# SCH_5_5-OLED-to-RP5-MIPI_2025-08-24.net
KiCad netlist of a schematic drawn in EasyEDA
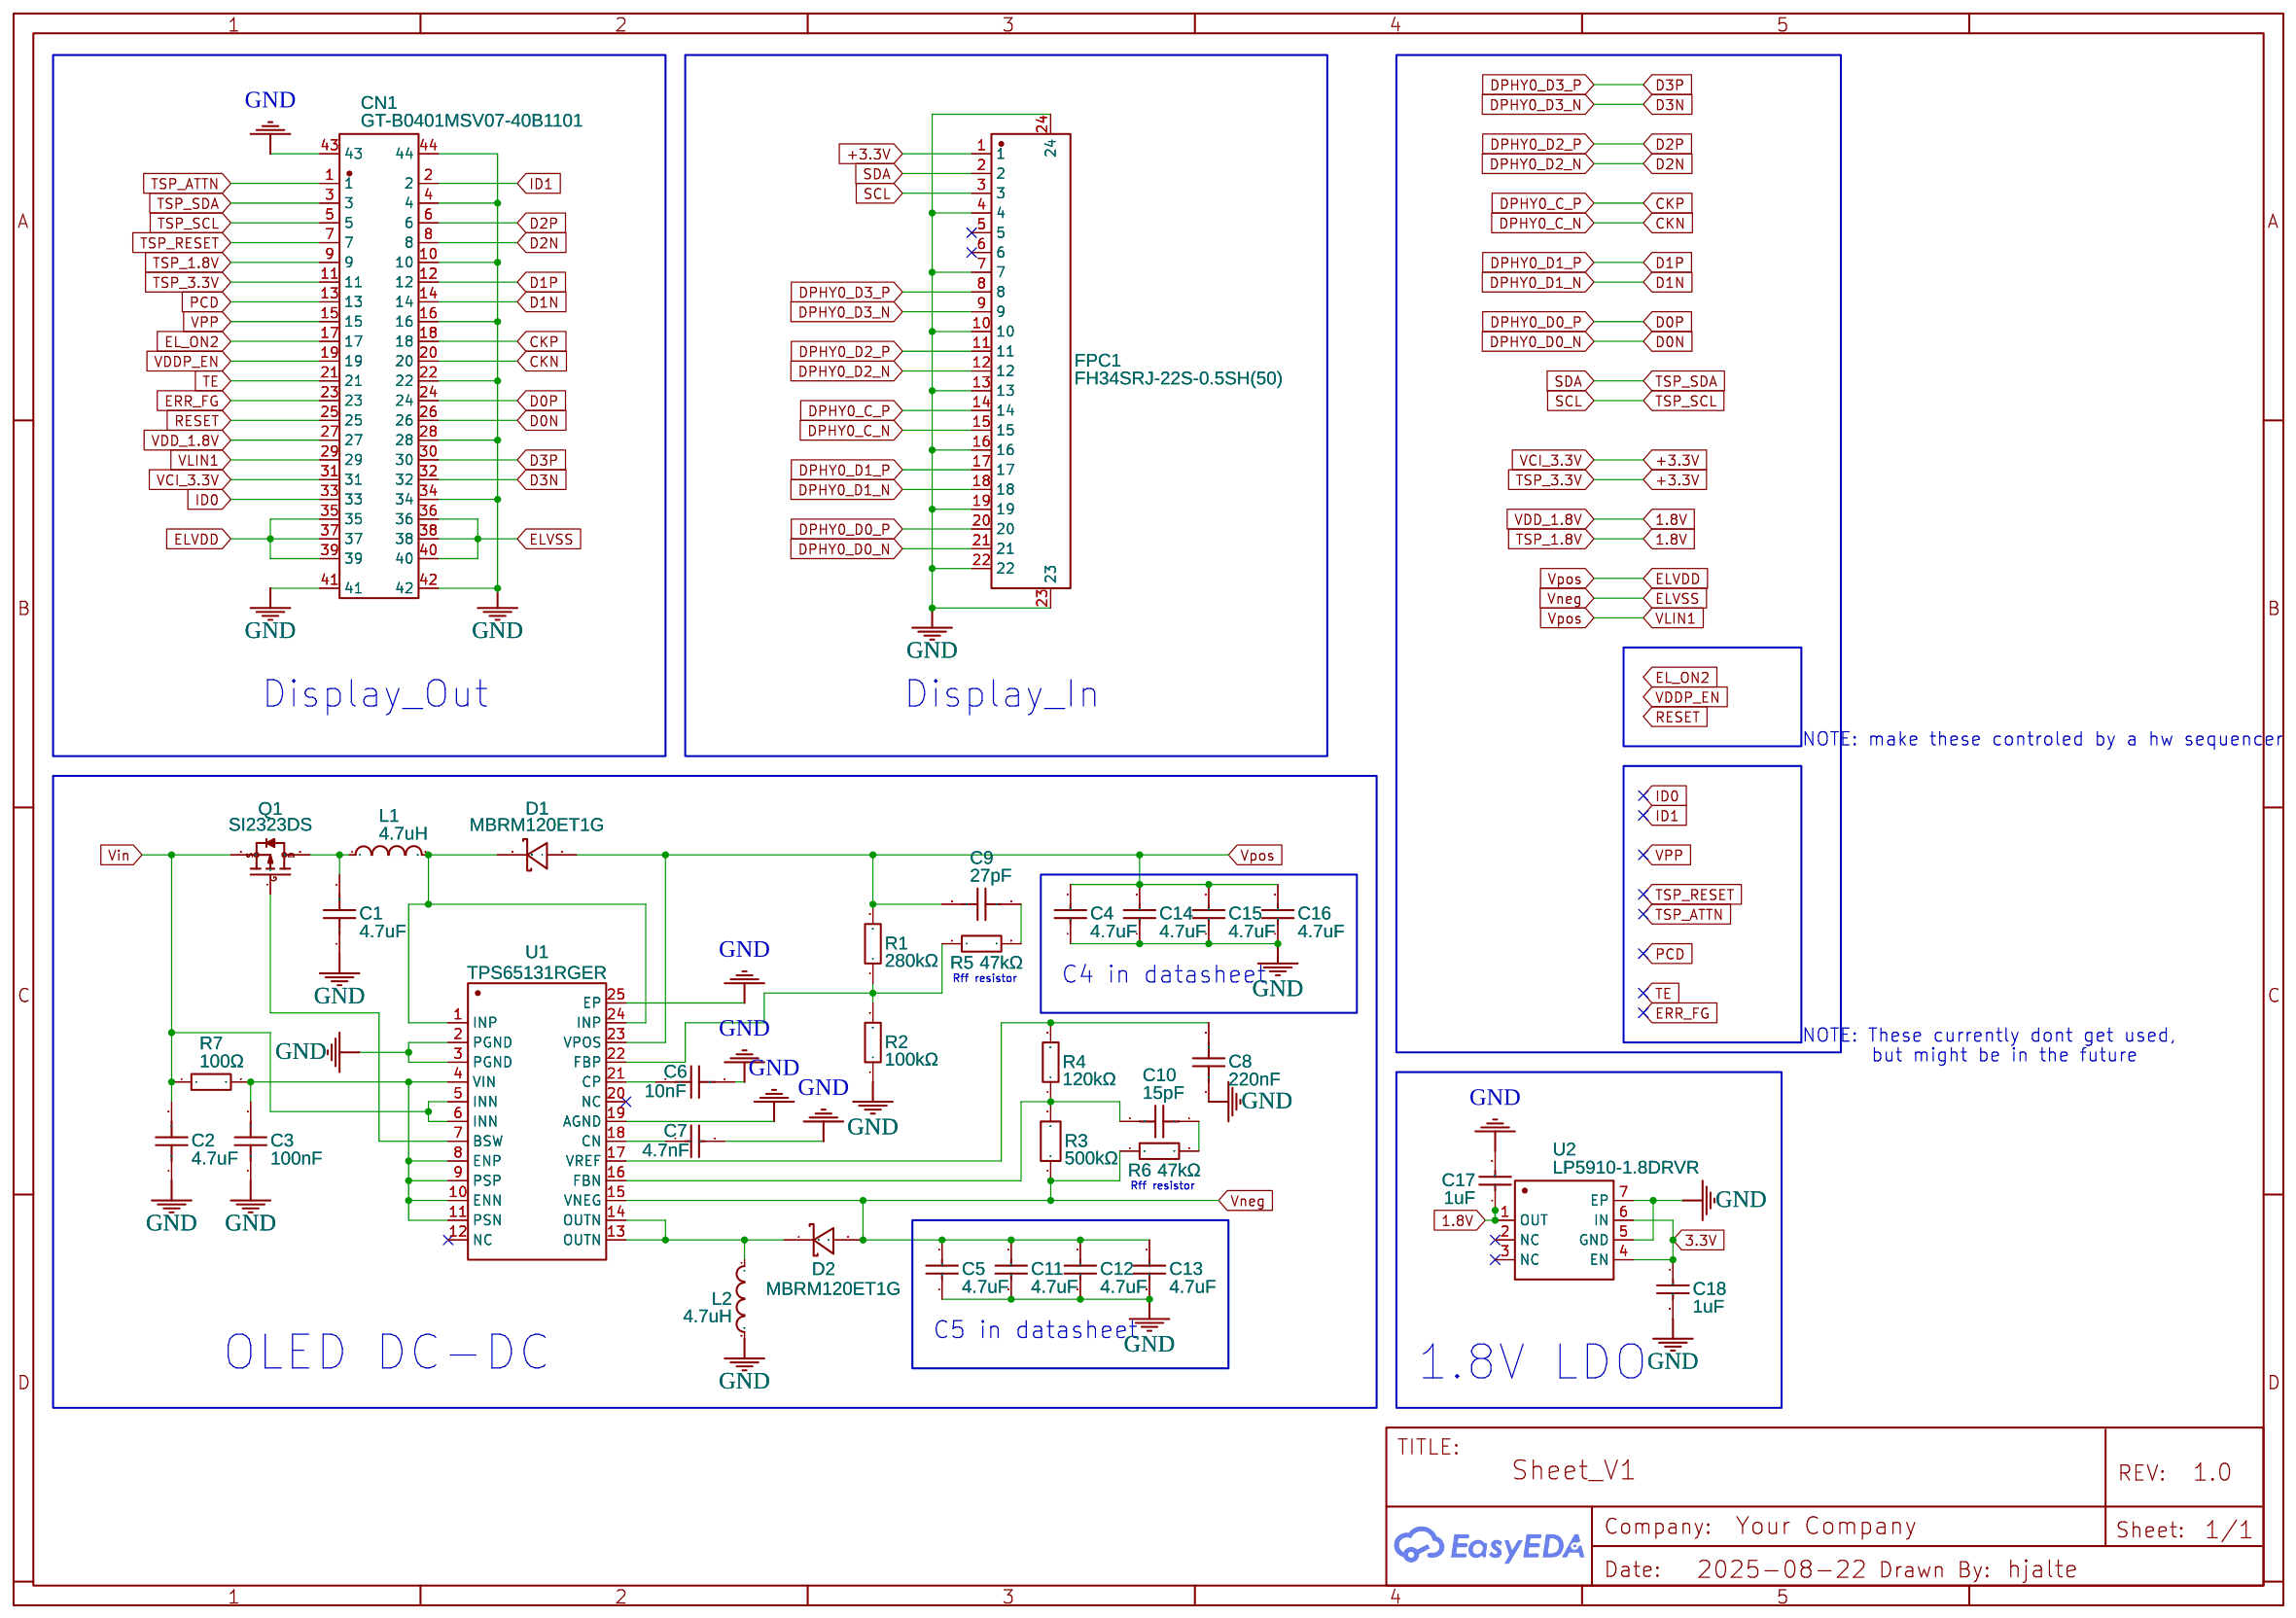
[diagram p0: schematic sheet]

(export (version "E")
  (design (tool "Eeschema 10.0.6"))
  (components
    (comp (ref "C1")
      (value "4.7uF")
      (fields
        (field (name "Manufacturer Part") "CL05A475MQ5NRNC")
        (field (name "Manufacturer") "SAMSUNG(三星)")
      )
      (libsource (lib "") (part "CL05A475MQ5NRNC_C307423"))
    )
    (comp (ref "C2")
      (value "4.7uF")
      (fields
        (field (name "Manufacturer Part") "CL05A475MQ5NRNC")
        (field (name "Manufacturer") "SAMSUNG(三星)")
      )
      (libsource (lib "") (part "CL05A475MQ5NRNC_C307423"))
    )
    (comp (ref "C3")
      (value "100nF")
      (fields
        (field (name "Manufacturer Part") "CL05B104KP5NNNC")
        (field (name "Manufacturer") "SAMSUNG(三星)")
      )
      (libsource (lib "") (part "CL05B104KP5NNNC"))
    )
    (comp (ref "C4")
      (value "4.7uF")
      (fields
        (field (name "Manufacturer Part") "CL21A475KAQNNNE")
        (field (name "Manufacturer") "SAMSUNG(三星)")
      )
      (libsource (lib "") (part "CL21A475KAQNNNE"))
    )
    (comp (ref "C5")
      (value "4.7uF")
      (fields
        (field (name "Manufacturer Part") "CL21A475KAQNNNE")
        (field (name "Manufacturer") "SAMSUNG(三星)")
      )
      (libsource (lib "") (part "CL21A475KAQNNNE"))
    )
    (comp (ref "C6")
      (value "10nF")
      (fields
        (field (name "Manufacturer Part") "CL05B103KO5NNNC")
        (field (name "Manufacturer") "SAMSUNG(三星)")
      )
      (libsource (lib "") (part "CL05B103KO5NNNC"))
    )
    (comp (ref "C7")
      (value "4.7nF")
      (fields
        (field (name "Manufacturer Part") "CL10B472KB8NNNC")
        (field (name "Manufacturer") "SAMSUNG(三星)")
      )
      (libsource (lib "") (part "CL10B472KB8NNNC"))
    )
    (comp (ref "C8")
      (value "220nF")
      (fields
        (field (name "Manufacturer Part") "CL05A224KQ5NNNC")
        (field (name "Manufacturer") "SAMSUNG(三星)")
      )
      (libsource (lib "") (part "CL05A224KQ5NNNC"))
    )
    (comp (ref "C9")
      (value "27pF")
      (fields
        (field (name "Manufacturer Part") "CC0603JRNPO7BN270")
        (field (name "Manufacturer") "YAGEO(国巨)")
      )
      (libsource (lib "") (part "CC0603JRNPO7BN270"))
    )
    (comp (ref "C10")
      (value "15pF")
      (fields
        (field (name "Manufacturer Part") "CC0402KRNPO7BN150")
        (field (name "Manufacturer") "YAGEO(国巨)")
      )
      (libsource (lib "") (part "CC0402KRNPO7BN150"))
    )
    (comp (ref "C11")
      (value "4.7uF")
      (fields
        (field (name "Manufacturer Part") "CL21A475KAQNNNE")
        (field (name "Manufacturer") "SAMSUNG(三星)")
      )
      (libsource (lib "") (part "CL21A475KAQNNNE"))
    )
    (comp (ref "C12")
      (value "4.7uF")
      (fields
        (field (name "Manufacturer Part") "CL21A475KAQNNNE")
        (field (name "Manufacturer") "SAMSUNG(三星)")
      )
      (libsource (lib "") (part "CL21A475KAQNNNE"))
    )
    (comp (ref "C13")
      (value "4.7uF")
      (fields
        (field (name "Manufacturer Part") "CL21A475KAQNNNE")
        (field (name "Manufacturer") "SAMSUNG(三星)")
      )
      (libsource (lib "") (part "CL21A475KAQNNNE"))
    )
    (comp (ref "C14")
      (value "4.7uF")
      (fields
        (field (name "Manufacturer Part") "CL21A475KAQNNNE")
        (field (name "Manufacturer") "SAMSUNG(三星)")
      )
      (libsource (lib "") (part "CL21A475KAQNNNE"))
    )
    (comp (ref "C15")
      (value "4.7uF")
      (fields
        (field (name "Manufacturer Part") "CL21A475KAQNNNE")
        (field (name "Manufacturer") "SAMSUNG(三星)")
      )
      (libsource (lib "") (part "CL21A475KAQNNNE"))
    )
    (comp (ref "C16")
      (value "4.7uF")
      (fields
        (field (name "Manufacturer Part") "CL21A475KAQNNNE")
        (field (name "Manufacturer") "SAMSUNG(三星)")
      )
      (libsource (lib "") (part "CL21A475KAQNNNE"))
    )
    (comp (ref "C17")
      (value "1uF")
      (fields
        (field (name "Manufacturer Part") "CL10A105KO8NNNC")
        (field (name "Manufacturer") "SAMSUNG(三星)")
      )
      (libsource (lib "") (part "CL10A105KO8NNNC"))
    )
    (comp (ref "C18")
      (value "1uF")
      (fields
        (field (name "Manufacturer Part") "CL10A105KO8NNNC")
        (field (name "Manufacturer") "SAMSUNG(三星)")
      )
      (libsource (lib "") (part "CL10A105KO8NNNC_1"))
    )
    (comp (ref "CN1")
      (value "GT-B0401MSV07-40B1101")
      (fields (field (name "Manufacturer") "G-Switch(品赞)"))
      (libsource (lib "") (part "GT-B0401MSV07-40B1101"))
    )
    (comp (ref "D1")
      (value "MBRM120ET1G")
      (fields (field (name "Manufacturer") "onsemi(安森美)"))
      (libsource (lib "") (part "MBRM120ET1G"))
    )
    (comp (ref "D2")
      (value "MBRM120ET1G")
      (fields (field (name "Manufacturer") "onsemi(安森美)"))
      (libsource (lib "") (part "MBRM120ET1G"))
    )
    (comp (ref "FPC1")
      (value "FH34SRJ-22S-0.5SH(50)")
      (fields (field (name "Manufacturer") "HRS(广濑)"))
      (libsource (lib "") (part "FH34SRJ-22S-0.5SH(50)"))
    )
    (comp (ref "L1")
      (value "4.7uH")
      (fields (field (name "Manufacturer Part") "FNR4020S4R7MT") (field (name "Manufacturer") "cjiang(长江微电)"))
      (libsource (lib "") (part "FNR4020S4R7MT_1"))
    )
    (comp (ref "L2")
      (value "4.7uH")
      (fields (field (name "Manufacturer Part") "FNR4020S4R7MT") (field (name "Manufacturer") "cjiang(长江微电)"))
      (libsource (lib "") (part "FNR4020S4R7MT"))
    )
    (comp (ref "Q1")
      (value "SI2323DS")
      (fields (field (name "Manufacturer") "TECH PUBLIC(台舟)"))
      (libsource (lib "") (part "SI2323DS"))
    )
    (comp (ref "R1")
      (value "280kΩ")
      (fields
        (field (name "Manufacturer Part") "0603WAF2803T5E")
        (field (name "Manufacturer") "UNI-ROYAL(厚声)")
      )
      (libsource (lib "") (part "0603WAF2803T5E"))
    )
    (comp (ref "R2")
      (value "100kΩ")
      (fields
        (field (name "Manufacturer Part") "0603WAF1003T5E")
        (field (name "Manufacturer") "UNI-ROYAL(厚声)")
      )
      (libsource (lib "") (part "0603WAF1003T5E"))
    )
    (comp (ref "R3")
      (value "500kΩ")
      (fields (field (name "Manufacturer Part") "AR03BTCX5003N") (field (name "Manufacturer") "Viking(光颉)"))
      (libsource (lib "") (part "AR03BTCX5003N"))
    )
    (comp (ref "R4")
      (value "120kΩ")
      (fields
        (field (name "Manufacturer Part") "0603WAF1203T5E")
        (field (name "Manufacturer") "UNI-ROYAL(厚声)")
      )
      (libsource (lib "") (part "0603WAF1203T5E"))
    )
    (comp (ref "R5")
      (value "47kΩ")
      (fields (field (name "Manufacturer Part") "RC0603FR-0747KL") (field (name "Manufacturer") "YAGEO(国巨)"))
      (libsource (lib "") (part "RC0603FR-0747KL"))
    )
    (comp (ref "R6")
      (value "47kΩ")
      (fields (field (name "Manufacturer Part") "RC0603FR-0747KL") (field (name "Manufacturer") "YAGEO(国巨)"))
      (libsource (lib "") (part "RC0603FR-0747KL"))
    )
    (comp (ref "R7")
      (value "100Ω")
      (fields (field (name "Manufacturer Part") "RC0402FR-07100RL") (field (name "Manufacturer") "YAGEO(国巨)"))
      (libsource (lib "") (part "RC0402FR-07100RL"))
    )
    (comp (ref "U1")
      (value "TPS65131RGER")
      (fields (field (name "Manufacturer") "TI(德州仪器)"))
      (libsource (lib "") (part "TPS65131RGER"))
    )
    (comp (ref "U2")
      (value "LP5910-1.8DRVR")
      (fields (field (name "Manufacturer") "TI(德州仪器)"))
      (libsource (lib "") (part "LP5910-1.8DRVR"))
    )
  )
  (nets
    (net (code "1") (name "+3.3V") (class "Default")
      (node (ref "CN1") (pin "11") (pinfunction "11_11") (pintype "unspecified"))
      (node (ref "CN1") (pin "31") (pinfunction "31_31") (pintype "unspecified"))
      (node (ref "FPC1") (pin "1") (pinfunction "1_1") (pintype "unspecified"))
    )
    (net (code "2") (name "1.8V") (class "Default")
      (node (ref "C17") (pin "1") (pinfunction "1_1") (pintype "input"))
      (node (ref "CN1") (pin "27") (pinfunction "27_27") (pintype "unspecified"))
      (node (ref "CN1") (pin "9") (pinfunction "9_9") (pintype "unspecified"))
      (node (ref "U2") (pin "1") (pinfunction "OUT_1") (pintype "unspecified"))
    )
    (net (code "3") (name "3.3V") (class "Default")
      (node (ref "C18") (pin "1") (pinfunction "1_1") (pintype "input"))
      (node (ref "U2") (pin "4") (pinfunction "EN_4") (pintype "unspecified"))
      (node (ref "U2") (pin "6") (pinfunction "IN_6") (pintype "unspecified"))
    )
    (net (code "4") (name "CKN") (class "Default")
      (node (ref "CN1") (pin "20") (pinfunction "20_20") (pintype "unspecified"))
      (node (ref "FPC1") (pin "15") (pinfunction "15_15") (pintype "unspecified"))
    )
    (net (code "5") (name "CKP") (class "Default")
      (node (ref "CN1") (pin "18") (pinfunction "18_18") (pintype "unspecified"))
      (node (ref "FPC1") (pin "14") (pinfunction "14_14") (pintype "unspecified"))
    )
    (net (code "6") (name "D0N") (class "Default")
      (node (ref "CN1") (pin "26") (pinfunction "26_26") (pintype "unspecified"))
      (node (ref "FPC1") (pin "21") (pinfunction "21_21") (pintype "unspecified"))
    )
    (net (code "7") (name "D0P") (class "Default")
      (node (ref "CN1") (pin "24") (pinfunction "24_24") (pintype "unspecified"))
      (node (ref "FPC1") (pin "20") (pinfunction "20_20") (pintype "unspecified"))
    )
    (net (code "8") (name "D1N") (class "Default")
      (node (ref "CN1") (pin "14") (pinfunction "14_14") (pintype "unspecified"))
      (node (ref "FPC1") (pin "18") (pinfunction "18_18") (pintype "unspecified"))
    )
    (net (code "9") (name "D1P") (class "Default")
      (node (ref "CN1") (pin "12") (pinfunction "12_12") (pintype "unspecified"))
      (node (ref "FPC1") (pin "17") (pinfunction "17_17") (pintype "unspecified"))
    )
    (net (code "10") (name "D2N") (class "Default")
      (node (ref "CN1") (pin "8") (pinfunction "8_8") (pintype "unspecified"))
      (node (ref "FPC1") (pin "12") (pinfunction "12_12") (pintype "unspecified"))
    )
    (net (code "11") (name "D2P") (class "Default")
      (node (ref "CN1") (pin "6") (pinfunction "6_6") (pintype "unspecified"))
      (node (ref "FPC1") (pin "11") (pinfunction "11_11") (pintype "unspecified"))
    )
    (net (code "12") (name "D3N") (class "Default")
      (node (ref "CN1") (pin "32") (pinfunction "32_32") (pintype "unspecified"))
      (node (ref "FPC1") (pin "9") (pinfunction "9_9") (pintype "unspecified"))
    )
    (net (code "13") (name "D3P") (class "Default")
      (node (ref "CN1") (pin "30") (pinfunction "30_30") (pintype "unspecified"))
      (node (ref "FPC1") (pin "8") (pinfunction "8_8") (pintype "unspecified"))
    )
    (net (code "14") (name "ELVDD") (class "Default")
      (node (ref "C14") (pin "2") (pinfunction "2_2") (pintype "input"))
      (node (ref "C15") (pin "2") (pinfunction "2_2") (pintype "input"))
      (node (ref "C16") (pin "2") (pinfunction "2_2") (pintype "input"))
      (node (ref "C4") (pin "2") (pinfunction "2_2") (pintype "input"))
      (node (ref "C9") (pin "2") (pinfunction "2_2") (pintype "unspecified"))
      (node (ref "CN1") (pin "29") (pinfunction "29_29") (pintype "unspecified"))
      (node (ref "CN1") (pin "35") (pinfunction "35_35") (pintype "unspecified"))
      (node (ref "CN1") (pin "37") (pinfunction "37_37") (pintype "unspecified"))
      (node (ref "CN1") (pin "39") (pinfunction "39_39") (pintype "unspecified"))
      (node (ref "D1") (pin "2") (pinfunction "A_2") (pintype "unspecified"))
      (node (ref "R1") (pin "2") (pinfunction "2_2") (pintype "input"))
      (node (ref "U1") (pin "23") (pinfunction "VPOS_23") (pintype "unspecified"))
    )
    (net (code "15") (name "ELVSS") (class "Default")
      (node (ref "C11") (pin "2") (pinfunction "2_2") (pintype "input"))
      (node (ref "C12") (pin "2") (pinfunction "2_2") (pintype "input"))
      (node (ref "C13") (pin "2") (pinfunction "2_2") (pintype "input"))
      (node (ref "C5") (pin "2") (pinfunction "2_2") (pintype "input"))
      (node (ref "CN1") (pin "36") (pinfunction "36_36") (pintype "unspecified"))
      (node (ref "CN1") (pin "38") (pinfunction "38_38") (pintype "unspecified"))
      (node (ref "CN1") (pin "40") (pinfunction "40_40") (pintype "unspecified"))
      (node (ref "D2") (pin "2") (pinfunction "A_2") (pintype "unspecified"))
      (node (ref "R3") (pin "1") (pinfunction "1_1") (pintype "unspecified"))
      (node (ref "R6") (pin "1") (pinfunction "1_1") (pintype "input"))
      (node (ref "U1") (pin "15") (pinfunction "VNEG_15") (pintype "unspecified"))
    )
    (net (code "16") (name "EL_ON2") (class "Default")
      (node (ref "CN1") (pin "17") (pinfunction "17_17") (pintype "unspecified"))
    )
    (net (code "17") (name "ERR_FG") (class "Default")
      (node (ref "CN1") (pin "23") (pinfunction "23_23") (pintype "unspecified+no_connect"))
    )
    (net (code "18") (name "GND") (class "Default")
      (node (ref "C1") (pin "1") (pinfunction "1_1") (pintype "unspecified"))
      (node (ref "C11") (pin "1") (pinfunction "1_1") (pintype "input"))
      (node (ref "C12") (pin "1") (pinfunction "1_1") (pintype "input"))
      (node (ref "C13") (pin "1") (pinfunction "1_1") (pintype "input"))
      (node (ref "C14") (pin "1") (pinfunction "1_1") (pintype "input"))
      (node (ref "C15") (pin "1") (pinfunction "1_1") (pintype "input"))
      (node (ref "C16") (pin "1") (pinfunction "1_1") (pintype "input"))
      (node (ref "C17") (pin "2") (pinfunction "2_2") (pintype "input"))
      (node (ref "C18") (pin "2") (pinfunction "2_2") (pintype "input"))
      (node (ref "C2") (pin "1") (pinfunction "1_1") (pintype "unspecified"))
      (node (ref "C3") (pin "1") (pinfunction "1_1") (pintype "unspecified"))
      (node (ref "C4") (pin "1") (pinfunction "1_1") (pintype "input"))
      (node (ref "C5") (pin "1") (pinfunction "1_1") (pintype "input"))
      (node (ref "C6") (pin "2") (pinfunction "2_2") (pintype "unspecified"))
      (node (ref "C7") (pin "2") (pinfunction "2_2") (pintype "input"))
      (node (ref "C8") (pin "1") (pinfunction "1_1") (pintype "unspecified"))
      (node (ref "CN1") (pin "10") (pinfunction "10_10") (pintype "unspecified"))
      (node (ref "CN1") (pin "16") (pinfunction "16_16") (pintype "unspecified"))
      (node (ref "CN1") (pin "22") (pinfunction "22_22") (pintype "unspecified"))
      (node (ref "CN1") (pin "28") (pinfunction "28_28") (pintype "unspecified"))
      (node (ref "CN1") (pin "34") (pinfunction "34_34") (pintype "unspecified"))
      (node (ref "CN1") (pin "4") (pinfunction "4_4") (pintype "unspecified"))
      (node (ref "CN1") (pin "41") (pinfunction "41_41") (pintype "unspecified"))
      (node (ref "CN1") (pin "42") (pinfunction "42_42") (pintype "unspecified"))
      (node (ref "CN1") (pin "43") (pinfunction "43_43") (pintype "unspecified"))
      (node (ref "CN1") (pin "44") (pinfunction "44_44") (pintype "unspecified"))
      (node (ref "FPC1") (pin "10") (pinfunction "10_10") (pintype "unspecified"))
      (node (ref "FPC1") (pin "13") (pinfunction "13_13") (pintype "unspecified"))
      (node (ref "FPC1") (pin "16") (pinfunction "16_16") (pintype "unspecified"))
      (node (ref "FPC1") (pin "19") (pinfunction "19_19") (pintype "unspecified"))
      (node (ref "FPC1") (pin "22") (pinfunction "22_22") (pintype "unspecified"))
      (node (ref "FPC1") (pin "23") (pinfunction "23_23") (pintype "unspecified"))
      (node (ref "FPC1") (pin "24") (pinfunction "24_24") (pintype "unspecified"))
      (node (ref "FPC1") (pin "4") (pinfunction "4_4") (pintype "unspecified"))
      (node (ref "FPC1") (pin "7") (pinfunction "7_7") (pintype "unspecified"))
      (node (ref "L2") (pin "2") (pinfunction "2_2") (pintype "unspecified"))
      (node (ref "R2") (pin "1") (pinfunction "1_1") (pintype "input"))
      (node (ref "U1") (pin "19") (pinfunction "AGND_19") (pintype "unspecified"))
      (node (ref "U1") (pin "2") (pinfunction "PGND_2") (pintype "unspecified"))
      (node (ref "U1") (pin "25") (pinfunction "EP_25") (pintype "unspecified"))
      (node (ref "U1") (pin "3") (pinfunction "PGND_3") (pintype "unspecified"))
      (node (ref "U2") (pin "5") (pinfunction "GND_5") (pintype "unspecified"))
      (node (ref "U2") (pin "7") (pinfunction "EP_7") (pintype "unspecified"))
    )
    (net (code "19") (name "ID0") (class "Default")
      (node (ref "CN1") (pin "33") (pinfunction "33_33") (pintype "unspecified+no_connect"))
    )
    (net (code "20") (name "ID1") (class "Default")
      (node (ref "CN1") (pin "2") (pinfunction "2_2") (pintype "unspecified+no_connect"))
    )
    (net (code "21") (name "Net-(C9-Pad1)") (class "Default")
      (node (ref "C9") (pin "1") (pinfunction "1_1") (pintype "unspecified"))
      (node (ref "R5") (pin "2") (pinfunction "2_2") (pintype "input"))
    )
    (net (code "22") (name "Net-(C10-Pad1)") (class "Default")
      (node (ref "C10") (pin "1") (pinfunction "1_1") (pintype "unspecified"))
      (node (ref "R6") (pin "2") (pinfunction "2_2") (pintype "input"))
    )
    (net (code "23") (name "Net-(D1-C)") (class "Default")
      (node (ref "D1") (pin "1") (pinfunction "C_1") (pintype "unspecified"))
      (node (ref "L1") (pin "2") (pinfunction "2_2") (pintype "unspecified"))
      (node (ref "U1") (pin "1") (pinfunction "INP_1") (pintype "unspecified"))
      (node (ref "U1") (pin "24") (pinfunction "INP_24") (pintype "unspecified"))
    )
    (net (code "24") (name "Net-(D2-C)") (class "Default")
      (node (ref "D2") (pin "1") (pinfunction "C_1") (pintype "unspecified"))
      (node (ref "L2") (pin "1") (pinfunction "1_1") (pintype "unspecified"))
      (node (ref "U1") (pin "13") (pinfunction "OUTN_13") (pintype "unspecified"))
      (node (ref "U1") (pin "14") (pinfunction "OUTN_14") (pintype "unspecified"))
    )
    (net (code "25") (name "Net-(Q1-D)") (class "Default")
      (node (ref "C1") (pin "2") (pinfunction "2_2") (pintype "unspecified"))
      (node (ref "L1") (pin "1") (pinfunction "1_1") (pintype "unspecified"))
      (node (ref "Q1") (pin "3") (pinfunction "D_3") (pintype "unspecified"))
    )
    (net (code "26") (name "Net-(Q1-G)") (class "Default")
      (node (ref "Q1") (pin "1") (pinfunction "G_1") (pintype "unspecified"))
      (node (ref "U1") (pin "7") (pinfunction "BSW_7") (pintype "unspecified"))
    )
    (net (code "27") (name "Net-(U1-CN)") (class "Default")
      (node (ref "C7") (pin "1") (pinfunction "1_1") (pintype "input"))
      (node (ref "U1") (pin "18") (pinfunction "CN_18") (pintype "unspecified"))
    )
    (net (code "28") (name "Net-(U1-CP)") (class "Default")
      (node (ref "C6") (pin "1") (pinfunction "1_1") (pintype "unspecified"))
      (node (ref "U1") (pin "21") (pinfunction "CP_21") (pintype "unspecified"))
    )
    (net (code "29") (name "Net-(U1-ENN)") (class "Default")
      (node (ref "C3") (pin "2") (pinfunction "2_2") (pintype "unspecified"))
      (node (ref "R7") (pin "2") (pinfunction "2_2") (pintype "input"))
      (node (ref "U1") (pin "10") (pinfunction "ENN_10") (pintype "unspecified"))
      (node (ref "U1") (pin "11") (pinfunction "PSN_11") (pintype "unspecified"))
      (node (ref "U1") (pin "4") (pinfunction "VIN_4") (pintype "unspecified"))
      (node (ref "U1") (pin "8") (pinfunction "ENP_8") (pintype "unspecified"))
      (node (ref "U1") (pin "9") (pinfunction "PSP_9") (pintype "unspecified"))
    )
    (net (code "30") (name "Net-(U1-FBN)") (class "Default")
      (node (ref "C10") (pin "2") (pinfunction "2_2") (pintype "unspecified"))
      (node (ref "R3") (pin "2") (pinfunction "2_2") (pintype "unspecified"))
      (node (ref "R4") (pin "1") (pinfunction "1_1") (pintype "input"))
      (node (ref "U1") (pin "16") (pinfunction "FBN_16") (pintype "unspecified"))
    )
    (net (code "31") (name "Net-(U1-FBP)") (class "Default")
      (node (ref "R1") (pin "1") (pinfunction "1_1") (pintype "input"))
      (node (ref "R2") (pin "2") (pinfunction "2_2") (pintype "input"))
      (node (ref "R5") (pin "1") (pinfunction "1_1") (pintype "input"))
      (node (ref "U1") (pin "22") (pinfunction "FBP_22") (pintype "unspecified"))
    )
    (net (code "32") (name "Net-(U1-VREF)") (class "Default")
      (node (ref "C8") (pin "2") (pinfunction "2_2") (pintype "unspecified"))
      (node (ref "R4") (pin "2") (pinfunction "2_2") (pintype "input"))
      (node (ref "U1") (pin "17") (pinfunction "VREF_17") (pintype "unspecified"))
    )
    (net (code "33") (name "PCD") (class "Default")
      (node (ref "CN1") (pin "13") (pinfunction "13_13") (pintype "unspecified+no_connect"))
    )
    (net (code "34") (name "RESET") (class "Default")
      (node (ref "CN1") (pin "25") (pinfunction "25_25") (pintype "unspecified"))
    )
    (net (code "35") (name "SCL") (class "Default")
      (node (ref "CN1") (pin "5") (pinfunction "5_5") (pintype "unspecified"))
      (node (ref "FPC1") (pin "3") (pinfunction "3_3") (pintype "unspecified"))
    )
    (net (code "36") (name "SDA") (class "Default")
      (node (ref "CN1") (pin "3") (pinfunction "3_3") (pintype "unspecified"))
      (node (ref "FPC1") (pin "2") (pinfunction "2_2") (pintype "unspecified"))
    )
    (net (code "37") (name "TE") (class "Default")
      (node (ref "CN1") (pin "21") (pinfunction "21_21") (pintype "unspecified+no_connect"))
    )
    (net (code "38") (name "TSP_ATTN") (class "Default")
      (node (ref "CN1") (pin "1") (pinfunction "1_1") (pintype "unspecified+no_connect"))
    )
    (net (code "39") (name "TSP_RESET") (class "Default")
      (node (ref "CN1") (pin "7") (pinfunction "7_7") (pintype "unspecified+no_connect"))
    )
    (net (code "40") (name "VDDP_EN") (class "Default")
      (node (ref "CN1") (pin "19") (pinfunction "19_19") (pintype "unspecified"))
    )
    (net (code "41") (name "VPP") (class "Default")
      (node (ref "CN1") (pin "15") (pinfunction "15_15") (pintype "unspecified+no_connect"))
    )
    (net (code "42") (name "Vin") (class "Default")
      (node (ref "C2") (pin "2") (pinfunction "2_2") (pintype "unspecified"))
      (node (ref "Q1") (pin "2") (pinfunction "S_2") (pintype "unspecified"))
      (node (ref "R7") (pin "1") (pinfunction "1_1") (pintype "input"))
      (node (ref "U1") (pin "5") (pinfunction "INN_5") (pintype "unspecified"))
      (node (ref "U1") (pin "6") (pinfunction "INN_6") (pintype "unspecified"))
    )
    (net (code "43") (name "unconnected-(FPC1-Pad5)") (class "Default")
      (node (ref "FPC1") (pin "5") (pinfunction "5_5") (pintype "unspecified+no_connect"))
    )
    (net (code "44") (name "unconnected-(FPC1-Pad6)") (class "Default")
      (node (ref "FPC1") (pin "6") (pinfunction "6_6") (pintype "unspecified+no_connect"))
    )
    (net (code "45") (name "unconnected-(U1-NC-Pad12)") (class "Default")
      (node (ref "U1") (pin "12") (pinfunction "NC_12") (pintype "unspecified+no_connect"))
    )
    (net (code "46") (name "unconnected-(U1-NC-Pad20)") (class "Default")
      (node (ref "U1") (pin "20") (pinfunction "NC_20") (pintype "unspecified+no_connect"))
    )
    (net (code "47") (name "unconnected-(U2-NC-Pad2)") (class "Default")
      (node (ref "U2") (pin "2") (pinfunction "NC_2") (pintype "unspecified+no_connect"))
    )
    (net (code "48") (name "unconnected-(U2-NC-Pad3)") (class "Default")
      (node (ref "U2") (pin "3") (pinfunction "NC_3") (pintype "unspecified+no_connect"))
    )
  )
)
